# xmega_breakout.net
KiCad netlist of a schematic drawn in EAGLE
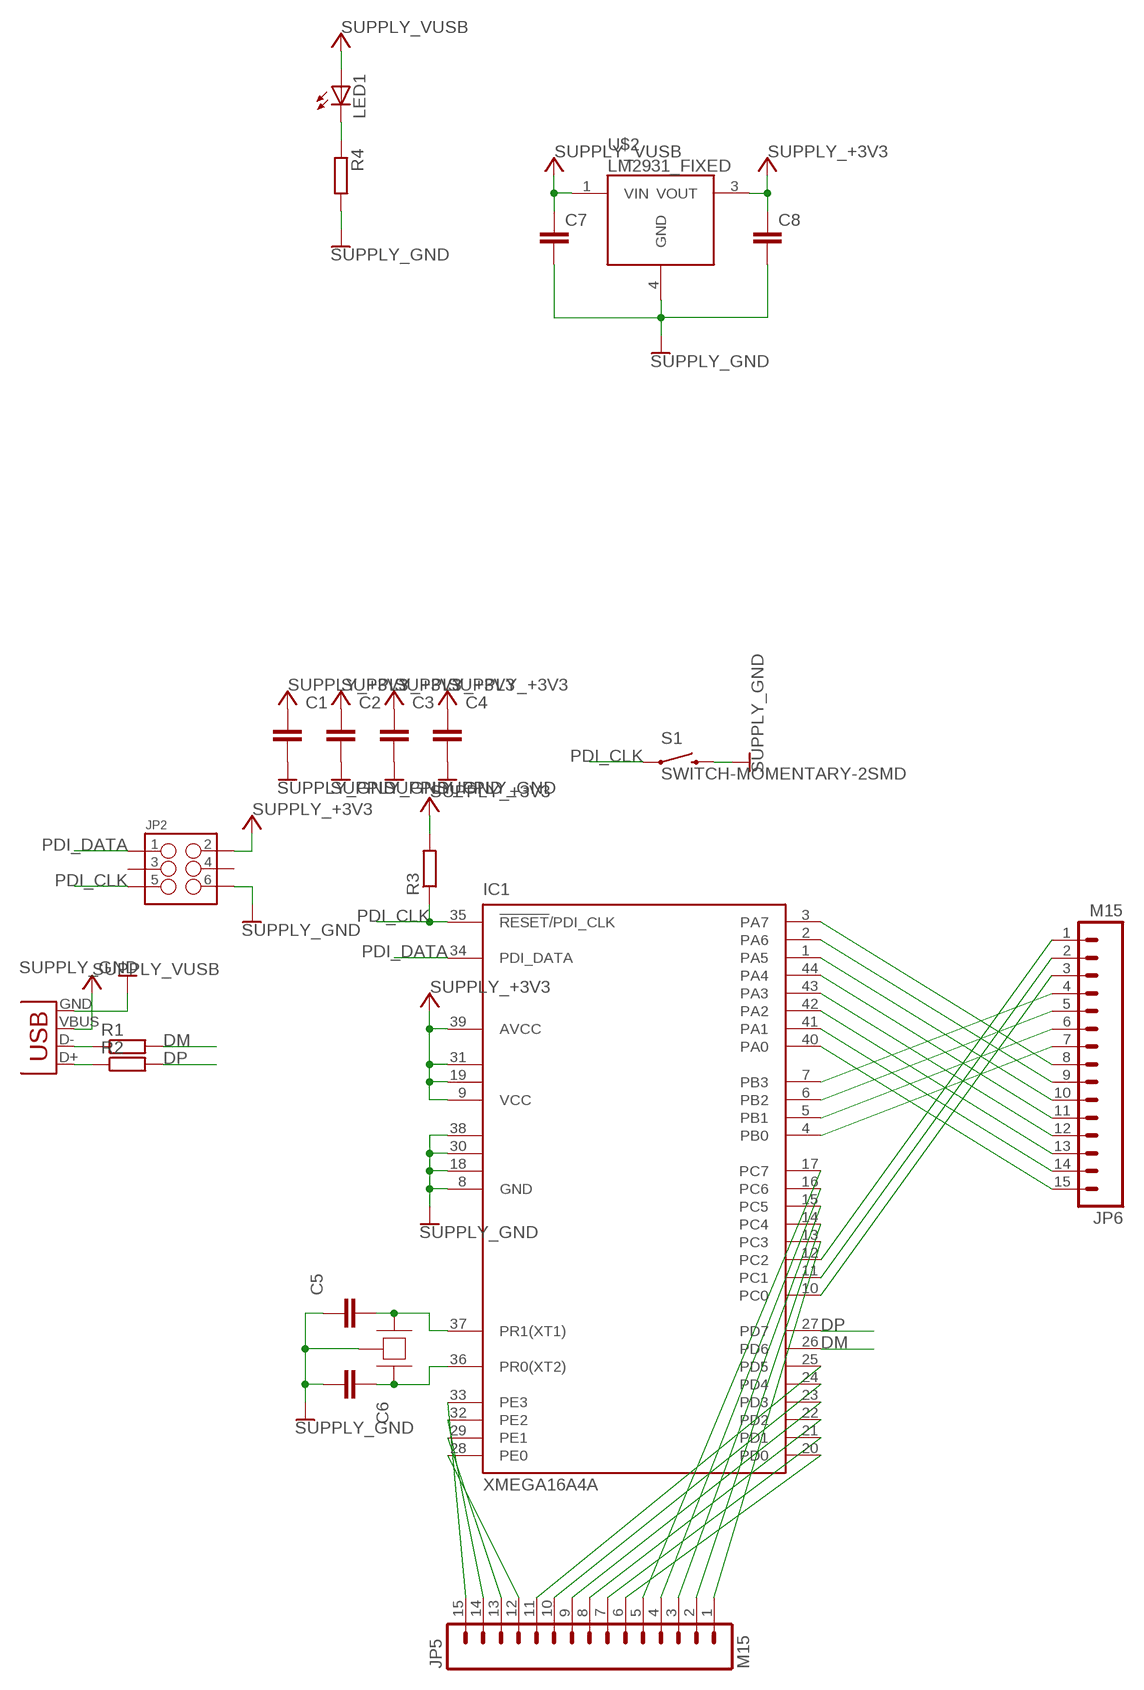
[diagram p0: schematic, sheet 1]

(export (version "E")
  (design (tool "Eeschema 10.0.6"))
  (components
    (comp (ref "C1")
      (value "CAPACITOR_NPOL-0402")
      (footprint "eagle-import:C402")
      (libsource (lib "eagle-import") (part "CAPACITOR_NPOL-0402"))
    )
    (comp (ref "C2")
      (value "CAPACITOR_NPOL-0402")
      (footprint "eagle-import:C402")
      (libsource (lib "eagle-import") (part "CAPACITOR_NPOL-0402"))
    )
    (comp (ref "C3")
      (value "CAPACITOR_NPOL-0402")
      (footprint "eagle-import:C402")
      (libsource (lib "eagle-import") (part "CAPACITOR_NPOL-0402"))
    )
    (comp (ref "C4")
      (value "CAPACITOR_NPOL-0402")
      (footprint "eagle-import:C402")
      (libsource (lib "eagle-import") (part "CAPACITOR_NPOL-0402"))
    )
    (comp (ref "C5")
      (value "CAPACITOR_NPOL-0402")
      (footprint "eagle-import:C402")
      (libsource (lib "eagle-import") (part "CAPACITOR_NPOL-0402"))
    )
    (comp (ref "C6")
      (value "CAPACITOR_NPOL-0402")
      (footprint "eagle-import:C402")
      (libsource (lib "eagle-import") (part "CAPACITOR_NPOL-0402"))
    )
    (comp (ref "C7")
      (value "C-EUC1210")
      (footprint "eagle-import:C1210")
      (libsource (lib "eagle-import") (part "C-EUC1210"))
    )
    (comp (ref "C8")
      (value "C-EUC1210")
      (footprint "eagle-import:C1210")
      (libsource (lib "eagle-import") (part "C-EUC1210"))
    )
    (comp (ref "IC1")
      (value "XMEGA16A4A")
      (footprint "eagle-import:TQFP44")
      (libsource (lib "eagle-import") (part "XMEGA16A4A"))
    )
    (comp (ref "JP1")
      (value "USBSMD")
      (footprint "eagle-import:USB-MINIB")
      (libsource (lib "eagle-import") (part "USBSMD"))
    )
    (comp (ref "JP2")
      (value "M03X22X3_SILK_SM")
      (footprint "eagle-import:2X3")
      (libsource (lib "eagle-import") (part "M03X22X3_SILK_SM"))
    )
    (comp (ref "JP5")
      (value "M15")
      (footprint "eagle-import:1X15")
      (libsource (lib "eagle-import") (part "M15"))
    )
    (comp (ref "JP6")
      (value "M15")
      (footprint "eagle-import:1X15")
      (libsource (lib "eagle-import") (part "M15"))
    )
    (comp (ref "LED1")
      (value "LED-0603")
      (footprint "eagle-import:LED-603")
      (libsource (lib "eagle-import") (part "LED-0603"))
    )
    (comp (ref "R1")
      (value "RESISTOR-0402")
      (footprint "eagle-import:R402")
      (libsource (lib "eagle-import") (part "RESISTOR-0402"))
    )
    (comp (ref "R2")
      (value "RESISTOR-0402")
      (footprint "eagle-import:R402")
      (libsource (lib "eagle-import") (part "RESISTOR-0402"))
    )
    (comp (ref "R3")
      (value "RESISTOR-0402")
      (footprint "eagle-import:R402")
      (libsource (lib "eagle-import") (part "RESISTOR-0402"))
    )
    (comp (ref "R4")
      (value "RESISTOR-0603")
      (footprint "eagle-import:R603")
      (libsource (lib "eagle-import") (part "RESISTOR-0603"))
    )
    (comp (ref "S1")
      (value "SWITCH-MOMENTARY-2SMD")
      (footprint "eagle-import:TACTILE_SWITCH_SMD")
      (libsource (lib "eagle-import") (part "SWITCH-MOMENTARY-2SMD"))
    )
    (comp (ref "U$1")
      (value "CRYSTAL-3.2X2.5")
      (footprint "eagle-import:TSX-3225")
      (libsource (lib "eagle-import") (part "CRYSTAL-3.2X2.5"))
    )
    (comp (ref "U$2")
      (value "LM2931_FIXED")
      (footprint "eagle-import:DPAK")
      (libsource (lib "eagle-import") (part "LM2931_FIXED"))
    )
  )
  (nets
    (net (code "1") (name "/DM") (class "Default")
      (node (ref "IC1") (pin "26") (pinfunction "PD6_26") (pintype "bidirectional"))
      (node (ref "R1") (pin "2") (pinfunction "2_2") (pintype "passive"))
    )
    (net (code "2") (name "/DP") (class "Default")
      (node (ref "IC1") (pin "27") (pinfunction "PD7_27") (pintype "bidirectional"))
      (node (ref "R2") (pin "2") (pinfunction "2_2") (pintype "passive"))
    )
    (net (code "3") (name "/PDI_CLK") (class "Default")
      (node (ref "IC1") (pin "35") (pinfunction "~{RESET}/PDI_CLK_35") (pintype "bidirectional"))
      (node (ref "JP2") (pin "5") (pinfunction "5_5") (pintype "bidirectional"))
      (node (ref "R3") (pin "1") (pinfunction "1_1") (pintype "passive"))
      (node (ref "S1") (pin "1") (pinfunction "1_1") (pintype "passive"))
    )
    (net (code "4") (name "/PDI_DATA") (class "Default")
      (node (ref "IC1") (pin "34") (pinfunction "PDI_DATA_34") (pintype "bidirectional"))
      (node (ref "JP2") (pin "1") (pinfunction "1_1") (pintype "bidirectional"))
    )
    (net (code "5") (name "Net-(IC1-PA0)") (class "Default")
      (node (ref "IC1") (pin "40") (pinfunction "PA0_40") (pintype "bidirectional"))
      (node (ref "JP6") (pin "15") (pinfunction "15_15") (pintype "passive"))
    )
    (net (code "6") (name "Net-(IC1-PA1)") (class "Default")
      (node (ref "IC1") (pin "41") (pinfunction "PA1_41") (pintype "bidirectional"))
      (node (ref "JP6") (pin "14") (pinfunction "14_14") (pintype "passive"))
    )
    (net (code "7") (name "Net-(IC1-PA2)") (class "Default")
      (node (ref "IC1") (pin "42") (pinfunction "PA2_42") (pintype "bidirectional"))
      (node (ref "JP6") (pin "13") (pinfunction "13_13") (pintype "passive"))
    )
    (net (code "8") (name "Net-(IC1-PA3)") (class "Default")
      (node (ref "IC1") (pin "43") (pinfunction "PA3_43") (pintype "bidirectional"))
      (node (ref "JP6") (pin "12") (pinfunction "12_12") (pintype "passive"))
    )
    (net (code "9") (name "Net-(IC1-PA4)") (class "Default")
      (node (ref "IC1") (pin "44") (pinfunction "PA4_44") (pintype "bidirectional"))
      (node (ref "JP6") (pin "11") (pinfunction "11_11") (pintype "passive"))
    )
    (net (code "10") (name "Net-(IC1-PA5)") (class "Default")
      (node (ref "IC1") (pin "1") (pinfunction "PA5_1") (pintype "bidirectional"))
      (node (ref "JP6") (pin "10") (pinfunction "10_10") (pintype "passive"))
    )
    (net (code "11") (name "Net-(IC1-PA6)") (class "Default")
      (node (ref "IC1") (pin "2") (pinfunction "PA6_2") (pintype "bidirectional"))
      (node (ref "JP6") (pin "9") (pinfunction "9_9") (pintype "passive"))
    )
    (net (code "12") (name "Net-(IC1-PA7)") (class "Default")
      (node (ref "IC1") (pin "3") (pinfunction "PA7_3") (pintype "bidirectional"))
      (node (ref "JP6") (pin "8") (pinfunction "8_8") (pintype "passive"))
    )
    (net (code "13") (name "Net-(IC1-PB0)") (class "Default")
      (node (ref "IC1") (pin "4") (pinfunction "PB0_4") (pintype "bidirectional"))
      (node (ref "JP6") (pin "7") (pinfunction "7_7") (pintype "passive"))
    )
    (net (code "14") (name "Net-(IC1-PB1)") (class "Default")
      (node (ref "IC1") (pin "5") (pinfunction "PB1_5") (pintype "bidirectional"))
      (node (ref "JP6") (pin "6") (pinfunction "6_6") (pintype "passive"))
    )
    (net (code "15") (name "Net-(IC1-PB2)") (class "Default")
      (node (ref "IC1") (pin "6") (pinfunction "PB2_6") (pintype "bidirectional"))
      (node (ref "JP6") (pin "5") (pinfunction "5_5") (pintype "passive"))
    )
    (net (code "16") (name "Net-(IC1-PB3)") (class "Default")
      (node (ref "IC1") (pin "7") (pinfunction "PB3_7") (pintype "bidirectional"))
      (node (ref "JP6") (pin "4") (pinfunction "4_4") (pintype "passive"))
    )
    (net (code "17") (name "Net-(IC1-PC0)") (class "Default")
      (node (ref "IC1") (pin "10") (pinfunction "PC0_10") (pintype "bidirectional"))
      (node (ref "JP6") (pin "3") (pinfunction "3_3") (pintype "passive"))
    )
    (net (code "18") (name "Net-(IC1-PC1)") (class "Default")
      (node (ref "IC1") (pin "11") (pinfunction "PC1_11") (pintype "bidirectional"))
      (node (ref "JP6") (pin "2") (pinfunction "2_2") (pintype "passive"))
    )
    (net (code "19") (name "Net-(IC1-PC2)") (class "Default")
      (node (ref "IC1") (pin "12") (pinfunction "PC2_12") (pintype "bidirectional"))
      (node (ref "JP6") (pin "1") (pinfunction "1_1") (pintype "passive"))
    )
    (net (code "20") (name "Net-(IC1-PC3)") (class "Default")
      (node (ref "IC1") (pin "13") (pinfunction "PC3_13") (pintype "bidirectional"))
      (node (ref "JP5") (pin "1") (pinfunction "1_1") (pintype "passive"))
    )
    (net (code "21") (name "Net-(IC1-PC4)") (class "Default")
      (node (ref "IC1") (pin "14") (pinfunction "PC4_14") (pintype "bidirectional"))
      (node (ref "JP5") (pin "2") (pinfunction "2_2") (pintype "passive"))
    )
    (net (code "22") (name "Net-(IC1-PC5)") (class "Default")
      (node (ref "IC1") (pin "15") (pinfunction "PC5_15") (pintype "bidirectional"))
      (node (ref "JP5") (pin "3") (pinfunction "3_3") (pintype "passive"))
    )
    (net (code "23") (name "Net-(IC1-PC6)") (class "Default")
      (node (ref "IC1") (pin "16") (pinfunction "PC6_16") (pintype "bidirectional"))
      (node (ref "JP5") (pin "4") (pinfunction "4_4") (pintype "passive"))
    )
    (net (code "24") (name "Net-(IC1-PC7)") (class "Default")
      (node (ref "IC1") (pin "17") (pinfunction "PC7_17") (pintype "bidirectional"))
      (node (ref "JP5") (pin "5") (pinfunction "5_5") (pintype "passive"))
    )
    (net (code "25") (name "Net-(IC1-PD0)") (class "Default")
      (node (ref "IC1") (pin "20") (pinfunction "PD0_20") (pintype "bidirectional"))
      (node (ref "JP5") (pin "6") (pinfunction "6_6") (pintype "passive"))
    )
    (net (code "26") (name "Net-(IC1-PD1)") (class "Default")
      (node (ref "IC1") (pin "21") (pinfunction "PD1_21") (pintype "bidirectional"))
      (node (ref "JP5") (pin "7") (pinfunction "7_7") (pintype "passive"))
    )
    (net (code "27") (name "Net-(IC1-PD2)") (class "Default")
      (node (ref "IC1") (pin "22") (pinfunction "PD2_22") (pintype "bidirectional"))
      (node (ref "JP5") (pin "8") (pinfunction "8_8") (pintype "passive"))
    )
    (net (code "28") (name "Net-(IC1-PD3)") (class "Default")
      (node (ref "IC1") (pin "23") (pinfunction "PD3_23") (pintype "bidirectional"))
      (node (ref "JP5") (pin "9") (pinfunction "9_9") (pintype "passive"))
    )
    (net (code "29") (name "Net-(IC1-PD4)") (class "Default")
      (node (ref "IC1") (pin "24") (pinfunction "PD4_24") (pintype "bidirectional"))
      (node (ref "JP5") (pin "10") (pinfunction "10_10") (pintype "passive"))
    )
    (net (code "30") (name "Net-(IC1-PD5)") (class "Default")
      (node (ref "IC1") (pin "25") (pinfunction "PD5_25") (pintype "bidirectional"))
      (node (ref "JP5") (pin "11") (pinfunction "11_11") (pintype "passive"))
    )
    (net (code "31") (name "Net-(IC1-PE0)") (class "Default")
      (node (ref "IC1") (pin "28") (pinfunction "PE0_28") (pintype "bidirectional"))
      (node (ref "JP5") (pin "12") (pinfunction "12_12") (pintype "passive"))
    )
    (net (code "32") (name "Net-(IC1-PE1)") (class "Default")
      (node (ref "IC1") (pin "29") (pinfunction "PE1_29") (pintype "bidirectional"))
      (node (ref "JP5") (pin "13") (pinfunction "13_13") (pintype "passive"))
    )
    (net (code "33") (name "Net-(IC1-PE2)") (class "Default")
      (node (ref "IC1") (pin "32") (pinfunction "PE2_32") (pintype "bidirectional"))
      (node (ref "JP5") (pin "14") (pinfunction "14_14") (pintype "passive"))
    )
    (net (code "34") (name "Net-(IC1-PE3)") (class "Default")
      (node (ref "IC1") (pin "33") (pinfunction "PE3_33") (pintype "bidirectional"))
      (node (ref "JP5") (pin "15") (pinfunction "15_15") (pintype "passive"))
    )
    (net (code "35") (name "Net-(IC1-PR0(XT2))") (class "Default")
      (node (ref "C6") (pin "1") (pinfunction "1_1") (pintype "passive"))
      (node (ref "IC1") (pin "36") (pinfunction "PR0(XT2)_36") (pintype "bidirectional"))
      (node (ref "U$1") (pin "C2") (pinfunction "C2_C2") (pintype "bidirectional"))
    )
    (net (code "36") (name "Net-(IC1-PR1(XT1))") (class "Default")
      (node (ref "C5") (pin "2") (pinfunction "2_2") (pintype "passive"))
      (node (ref "IC1") (pin "37") (pinfunction "PR1(XT1)_37") (pintype "bidirectional"))
      (node (ref "U$1") (pin "C1") (pinfunction "C1_C1") (pintype "bidirectional"))
    )
    (net (code "37") (name "Net-(JP1-PadD+)") (class "Default")
      (node (ref "JP1") (pin "D+") (pinfunction "D+_D+") (pintype "bidirectional"))
      (node (ref "R2") (pin "1") (pinfunction "1_1") (pintype "passive"))
    )
    (net (code "38") (name "Net-(JP1-PadD-)") (class "Default")
      (node (ref "JP1") (pin "D-") (pinfunction "D-_D-") (pintype "bidirectional"))
      (node (ref "R1") (pin "1") (pinfunction "1_1") (pintype "passive"))
    )
    (net (code "39") (name "Net-(LED1-PadC)") (class "Default")
      (node (ref "LED1") (pin "C") (pinfunction "C_C") (pintype "passive"))
      (node (ref "R4") (pin "1") (pinfunction "1_1") (pintype "passive"))
    )
    (net (code "40") (name "SUPPLY_+3V3") (class "Default")
      (node (ref "C1") (pin "1") (pinfunction "1_1") (pintype "passive"))
      (node (ref "C2") (pin "1") (pinfunction "1_1") (pintype "passive"))
      (node (ref "C3") (pin "1") (pinfunction "1_1") (pintype "passive"))
      (node (ref "C4") (pin "1") (pinfunction "1_1") (pintype "passive"))
      (node (ref "C8") (pin "1") (pinfunction "1_1") (pintype "passive"))
      (node (ref "IC1") (pin "19") (pinfunction "VCC1_19") (pintype "power_in"))
      (node (ref "IC1") (pin "31") (pinfunction "VCC2_31") (pintype "power_in"))
      (node (ref "IC1") (pin "39") (pinfunction "AVCC_39") (pintype "power_in"))
      (node (ref "IC1") (pin "9") (pinfunction "VCC_9") (pintype "power_in"))
      (node (ref "JP2") (pin "2") (pinfunction "2_2") (pintype "bidirectional"))
      (node (ref "R3") (pin "2") (pinfunction "2_2") (pintype "passive"))
      (node (ref "U$2") (pin "3") (pinfunction "VOUT_3") (pintype "bidirectional"))
    )
    (net (code "41") (name "SUPPLY_GND") (class "Default")
      (node (ref "C1") (pin "2") (pinfunction "2_2") (pintype "passive"))
      (node (ref "C2") (pin "2") (pinfunction "2_2") (pintype "passive"))
      (node (ref "C3") (pin "2") (pinfunction "2_2") (pintype "passive"))
      (node (ref "C4") (pin "2") (pinfunction "2_2") (pintype "passive"))
      (node (ref "C5") (pin "1") (pinfunction "1_1") (pintype "passive"))
      (node (ref "C6") (pin "2") (pinfunction "2_2") (pintype "passive"))
      (node (ref "C7") (pin "2") (pinfunction "2_2") (pintype "passive"))
      (node (ref "C8") (pin "2") (pinfunction "2_2") (pintype "passive"))
      (node (ref "IC1") (pin "18") (pinfunction "GND1_18") (pintype "power_in"))
      (node (ref "IC1") (pin "30") (pinfunction "GND2_30") (pintype "power_in"))
      (node (ref "IC1") (pin "38") (pinfunction "GND3_38") (pintype "power_in"))
      (node (ref "IC1") (pin "8") (pinfunction "GND_8") (pintype "power_in"))
      (node (ref "JP1") (pin "GND") (pinfunction "GND_GND") (pintype "bidirectional"))
      (node (ref "JP2") (pin "6") (pinfunction "6_6") (pintype "bidirectional"))
      (node (ref "R4") (pin "2") (pinfunction "2_2") (pintype "passive"))
      (node (ref "S1") (pin "3") (pinfunction "2_3") (pintype "passive"))
      (node (ref "U$1") (pin "G1") (pinfunction "GND_G1") (pintype "power_in"))
      (node (ref "U$1") (pin "G2") (pinfunction "GND_G2") (pintype "power_in"))
      (node (ref "U$2") (pin "4") (pinfunction "GND_4") (pintype "bidirectional"))
    )
    (net (code "42") (name "SUPPLY_VUSB") (class "Default")
      (node (ref "C7") (pin "1") (pinfunction "1_1") (pintype "passive"))
      (node (ref "JP1") (pin "VBUS") (pinfunction "VBUS_VBUS") (pintype "bidirectional"))
      (node (ref "LED1") (pin "A") (pinfunction "A_A") (pintype "passive"))
      (node (ref "U$2") (pin "1") (pinfunction "VIN_1") (pintype "bidirectional"))
    )
    (net (code "43") (name "unconnected-(JP2-Pad3)") (class "Default")
      (node (ref "JP2") (pin "3") (pinfunction "3_3") (pintype "bidirectional"))
    )
    (net (code "44") (name "unconnected-(JP2-Pad4)") (class "Default")
      (node (ref "JP2") (pin "4") (pinfunction "4_4") (pintype "bidirectional"))
    )
  )
)
